# 06_Ethernet.net
KiCad netlist of a schematic drawn in Altium Designer
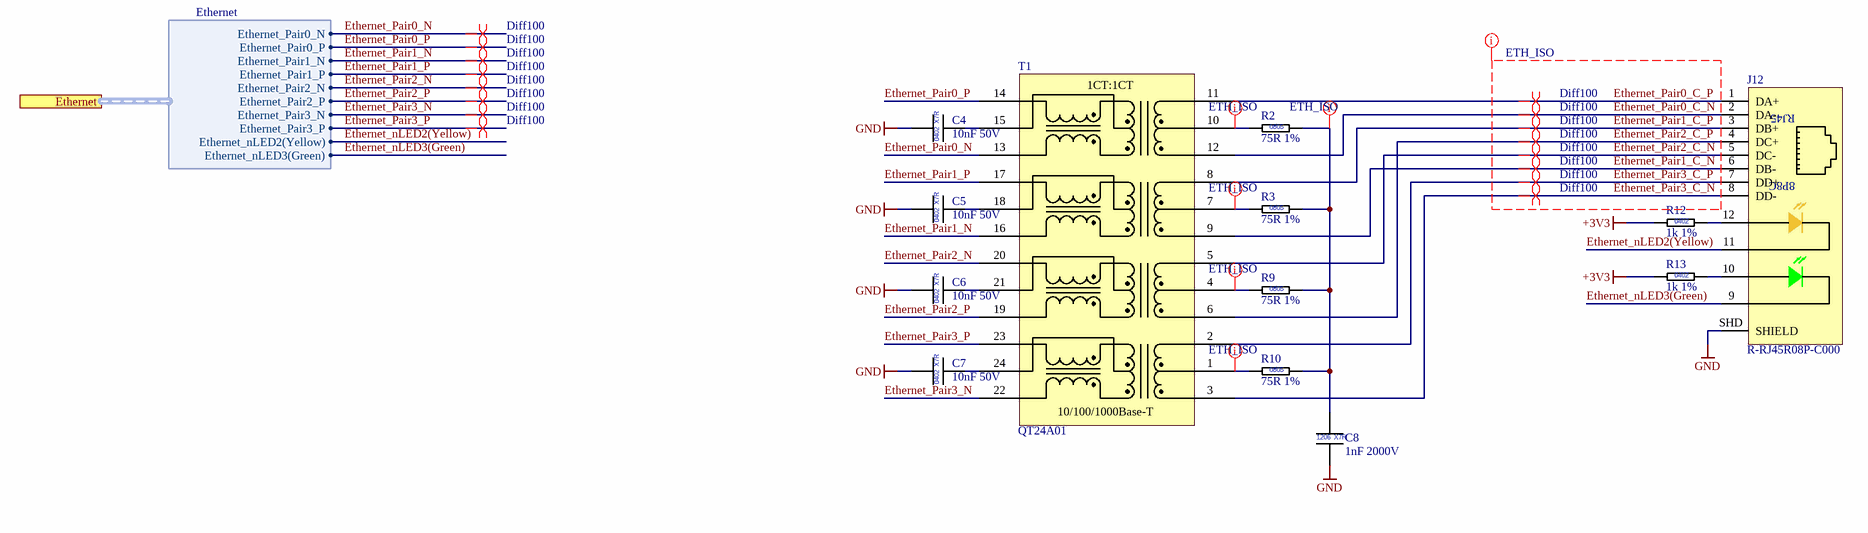
[diagram p0: 06_Ethernet.SchDoc]

(export (version "E")
  (design (tool "Eeschema 10.0.6"))
  (components
    (comp (ref "C4")
      (value "10nF 50V")
      (footprint "Cap:CAP_0402")
      (description "Multilayer Ceramic Capacitors MLCC - SMD/SMT 0402 50VDC")
      (libsource (lib "Cap") (part "CAP_0402_10nF_50V"))
    )
    (comp (ref "C5")
      (value "10nF 50V")
      (footprint "Cap:CAP_0402")
      (description "Multilayer Ceramic Capacitors MLCC - SMD/SMT 0402 50VDC")
      (libsource (lib "Cap") (part "CAP_0402_10nF_50V"))
    )
    (comp (ref "C6")
      (value "10nF 50V")
      (footprint "Cap:CAP_0402")
      (description "Multilayer Ceramic Capacitors MLCC - SMD/SMT 0402 50VDC")
      (libsource (lib "Cap") (part "CAP_0402_10nF_50V"))
    )
    (comp (ref "C7")
      (value "10nF 50V")
      (footprint "Cap:CAP_0402")
      (description "Multilayer Ceramic Capacitors MLCC - SMD/SMT 0402 50VDC")
      (libsource (lib "Cap") (part "CAP_0402_10nF_50V"))
    )
    (comp (ref "C8")
      (value "1nF 2000V")
      (footprint "Cap:CAP_1206")
      (description "Multilayer Ceramic Capacitors MLCC - SMD/SMT 1206 2000VDC")
      (libsource (lib "Cap") (part "CAP_1206_1nF_2000V"))
    )
    (comp (ref "J12")
      (value "R-RJ45R08P-C000")
      (footprint "Conn:Ckmtw - R-RJ45R08P-C000")
      (libsource (lib "Conn") (part "R-RJ45R08P-C000_RJ45 8P8C Shielded Yellow - Green Through Hole Ethernet Connectors"))
    )
    (comp (ref "R2")
      (value "75R 1%")
      (footprint "Res:RES_0805")
      (description "Thick Film Resistors - SMD 75Ohm 1%")
      (libsource (lib "Res") (part "RES_0805_75R_1%"))
    )
    (comp (ref "R3")
      (value "75R 1%")
      (footprint "Res:RES_0805")
      (description "Thick Film Resistors - SMD 75Ohm 1%")
      (libsource (lib "Res") (part "RES_0805_75R_1%"))
    )
    (comp (ref "R9")
      (value "75R 1%")
      (footprint "Res:RES_0805")
      (description "Thick Film Resistors - SMD 75Ohm 1%")
      (libsource (lib "Res") (part "RES_0805_75R_1%"))
    )
    (comp (ref "R10")
      (value "75R 1%")
      (footprint "Res:RES_0805")
      (description "Thick Film Resistors - SMD 75Ohm 1%")
      (libsource (lib "Res") (part "RES_0805_75R_1%"))
    )
    (comp (ref "R12")
      (value "1k 1%")
      (footprint "res:RES_0402")
      (description "Thick Film Resistors - SMD 1kOhm 1%")
      (libsource (lib "Res") (part "RES_0402_1k_1%"))
    )
    (comp (ref "R13")
      (value "1k 1%")
      (footprint "res:RES_0402")
      (description "Thick Film Resistors - SMD 1kOhm 1%")
      (libsource (lib "Res") (part "RES_0402_1k_1%"))
    )
    (comp (ref "T1")
      (value "QT24A01")
      (footprint "Indc:QT24A01")
      (description "1:1 350 28 1.2 -1 -16 SMD,24PIN RJ45 Transformer RoHS")
      (libsource (lib "Indc") (part "QT24A01_10/100/1000Base-T  Single  Port  Transformer"))
    )
  )
  (nets
    (net (code "2") (name "+3V3") (class "Default")
      (node (ref "R12") (pin "1") (pinfunction "1_1") (pintype "passive"))
      (node (ref "R13") (pin "1") (pinfunction "1_1") (pintype "passive"))
    )
    (net (code "3") (name "/Ethernet_Pair0_C_N") (class "Default")
      (node (ref "J12") (pin "2") (pinfunction "DA-_2") (pintype "passive"))
      (node (ref "T1") (pin "12") (pinfunction "TD4-_12") (pintype "passive"))
    )
    (net (code "4") (name "/Ethernet_Pair0_C_P") (class "Default")
      (node (ref "J12") (pin "1") (pinfunction "DA+_1") (pintype "passive"))
      (node (ref "T1") (pin "11") (pinfunction "TD4+_11") (pintype "passive"))
    )
    (net (code "5") (name "/Ethernet_Pair0_N") (class "Default")
      (node (ref "T1") (pin "13") (pinfunction "MX4-_13") (pintype "passive"))
    )
    (net (code "6") (name "/Ethernet_Pair0_P") (class "Default")
      (node (ref "T1") (pin "14") (pinfunction "MX4+_14") (pintype "passive"))
    )
    (net (code "7") (name "/Ethernet_Pair1_C_N") (class "Default")
      (node (ref "J12") (pin "6") (pinfunction "DB-_6") (pintype "passive"))
      (node (ref "T1") (pin "9") (pinfunction "TD3-_9") (pintype "passive"))
    )
    (net (code "8") (name "/Ethernet_Pair1_C_P") (class "Default")
      (node (ref "J12") (pin "3") (pinfunction "DB+_3") (pintype "passive"))
      (node (ref "T1") (pin "8") (pinfunction "TD3+_8") (pintype "passive"))
    )
    (net (code "9") (name "/Ethernet_Pair1_N") (class "Default")
      (node (ref "T1") (pin "16") (pinfunction "MX3-_16") (pintype "passive"))
    )
    (net (code "10") (name "/Ethernet_Pair1_P") (class "Default")
      (node (ref "T1") (pin "17") (pinfunction "MX3+_17") (pintype "passive"))
    )
    (net (code "11") (name "/Ethernet_Pair2_C_N") (class "Default")
      (node (ref "J12") (pin "5") (pinfunction "DC-_5") (pintype "passive"))
      (node (ref "T1") (pin "5") (pinfunction "TD2+_5") (pintype "passive"))
    )
    (net (code "12") (name "/Ethernet_Pair2_C_P") (class "Default")
      (node (ref "J12") (pin "4") (pinfunction "DC+_4") (pintype "passive"))
      (node (ref "T1") (pin "6") (pinfunction "TD2-_6") (pintype "passive"))
    )
    (net (code "13") (name "/Ethernet_Pair2_N") (class "Default")
      (node (ref "T1") (pin "20") (pinfunction "MX2+_20") (pintype "passive"))
    )
    (net (code "14") (name "/Ethernet_Pair2_P") (class "Default")
      (node (ref "T1") (pin "19") (pinfunction "MX2-_19") (pintype "passive"))
    )
    (net (code "15") (name "/Ethernet_Pair3_C_N") (class "Default")
      (node (ref "J12") (pin "8") (pinfunction "DD-_8") (pintype "passive"))
      (node (ref "T1") (pin "3") (pinfunction "TD1-_3") (pintype "passive"))
    )
    (net (code "16") (name "/Ethernet_Pair3_C_P") (class "Default")
      (node (ref "J12") (pin "7") (pinfunction "DD+_7") (pintype "passive"))
      (node (ref "T1") (pin "2") (pinfunction "TD1+_2") (pintype "passive"))
    )
    (net (code "17") (name "/Ethernet_Pair3_N") (class "Default")
      (node (ref "T1") (pin "22") (pinfunction "MX1-_22") (pintype "passive"))
    )
    (net (code "18") (name "/Ethernet_Pair3_P") (class "Default")
      (node (ref "T1") (pin "23") (pinfunction "MX1+_23") (pintype "passive"))
    )
    (net (code "19") (name "/Ethernet_nLED2(Yellow)") (class "Default")
      (node (ref "J12") (pin "11") (pinfunction "11_11") (pintype "passive"))
    )
    (net (code "20") (name "/Ethernet_nLED3(Green)") (class "Default")
      (node (ref "J12") (pin "9") (pinfunction "9_9") (pintype "passive"))
    )
    (net (code "22") (name "GND") (class "Default")
      (node (ref "C4") (pin "1") (pinfunction "1_1") (pintype "passive"))
      (node (ref "C5") (pin "1") (pinfunction "1_1") (pintype "passive"))
      (node (ref "C6") (pin "1") (pinfunction "1_1") (pintype "passive"))
      (node (ref "C7") (pin "1") (pinfunction "1_1") (pintype "passive"))
      (node (ref "C8") (pin "2") (pinfunction "2_2") (pintype "passive"))
      (node (ref "J12") (pin "SHD") (pinfunction "SHIELD_SHD") (pintype "passive"))
    )
    (net (code "23") (name "Net-(C8-Pad1)") (class "Default")
      (node (ref "C8") (pin "1") (pinfunction "1_1") (pintype "passive"))
      (node (ref "R10") (pin "2") (pinfunction "2_2") (pintype "passive"))
      (node (ref "R2") (pin "2") (pinfunction "2_2") (pintype "passive"))
      (node (ref "R3") (pin "2") (pinfunction "2_2") (pintype "passive"))
      (node (ref "R9") (pin "2") (pinfunction "2_2") (pintype "passive"))
    )
    (net (code "24") (name "Net-(J12-Pad10)") (class "Default")
      (node (ref "J12") (pin "10") (pinfunction "10_10") (pintype "passive"))
      (node (ref "R13") (pin "2") (pinfunction "2_2") (pintype "passive"))
    )
    (net (code "25") (name "Net-(J12-Pad12)") (class "Default")
      (node (ref "J12") (pin "12") (pinfunction "12_12") (pintype "passive"))
      (node (ref "R12") (pin "2") (pinfunction "2_2") (pintype "passive"))
    )
    (net (code "26") (name "Net-(T1-MCT1)") (class "Default")
      (node (ref "C7") (pin "2") (pinfunction "2_2") (pintype "passive"))
      (node (ref "T1") (pin "24") (pinfunction "MCT1_24") (pintype "passive"))
    )
    (net (code "27") (name "Net-(T1-MCT2)") (class "Default")
      (node (ref "C6") (pin "2") (pinfunction "2_2") (pintype "passive"))
      (node (ref "T1") (pin "21") (pinfunction "MCT2_21") (pintype "passive"))
    )
    (net (code "28") (name "Net-(T1-MCT3)") (class "Default")
      (node (ref "C5") (pin "2") (pinfunction "2_2") (pintype "passive"))
      (node (ref "T1") (pin "18") (pinfunction "MCT3_18") (pintype "passive"))
    )
    (net (code "29") (name "Net-(T1-MCT4)") (class "Default")
      (node (ref "C4") (pin "2") (pinfunction "2_2") (pintype "passive"))
      (node (ref "T1") (pin "15") (pinfunction "MCT4_15") (pintype "passive"))
    )
    (net (code "30") (name "Net-(T1-TCT1)") (class "Default")
      (node (ref "R10") (pin "1") (pinfunction "1_1") (pintype "passive"))
      (node (ref "T1") (pin "1") (pinfunction "TCT1_1") (pintype "passive"))
    )
    (net (code "31") (name "Net-(T1-TCT2)") (class "Default")
      (node (ref "R9") (pin "1") (pinfunction "1_1") (pintype "passive"))
      (node (ref "T1") (pin "4") (pinfunction "TCT2_4") (pintype "passive"))
    )
    (net (code "32") (name "Net-(T1-TCT3)") (class "Default")
      (node (ref "R3") (pin "1") (pinfunction "1_1") (pintype "passive"))
      (node (ref "T1") (pin "7") (pinfunction "TCT3_7") (pintype "passive"))
    )
    (net (code "33") (name "Net-(T1-TCT4)") (class "Default")
      (node (ref "R2") (pin "1") (pinfunction "1_1") (pintype "passive"))
      (node (ref "T1") (pin "10") (pinfunction "TCT4_10") (pintype "passive"))
    )
  )
)
